# 411618_029_3_7.net
KiCad netlist of a schematic drawn in Altium Designer
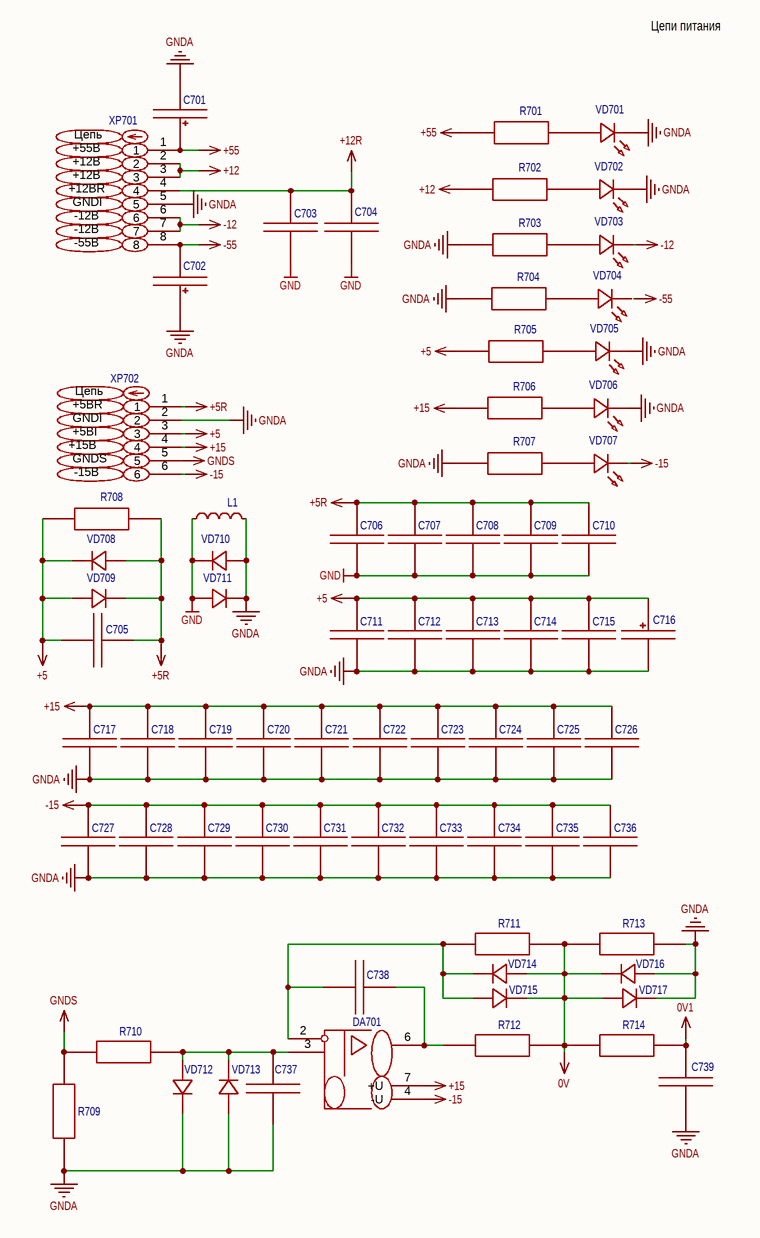
[diagram p0: УШЯИ.411618.029Э Э3 Лист 7.schdoc]

(export (version "E")
  (design (tool "Eeschema 10.0.6"))
  (components
    (comp (ref "C701")
      (value "ECAP (К50-35), 4.7мкФ, 100В, 105°C, 5x11, p:2мм")
      (footprint "CAP-TH_BD5.0-P2.00-D0.8-FD")
      (fields (field (name "MANUFACTURER") "Chengx") (field (name "CONTRIBUTOR") "jordanjin"))
      (libsource (lib "altium-import") (part "root_2_ECAP (К50-35), 4.7мкФ, 100В, 105°C, 5x11, p{colon}2мм_"))
    )
    (comp (ref "C702")
      (value "ECAP (К50-35), 4.7мкФ, 100В, 105°C, 5x11, p:2мм")
      (footprint "CAP-TH_BD5.0-P2.00-D0.8-FD")
      (fields (field (name "MANUFACTURER") "Chengx") (field (name "CONTRIBUTOR") "jordanjin"))
      (libsource (lib "altium-import") (part "root_2_ECAP (К50-35), 4.7мкФ, 100В, 105°C, 5x11, p{colon}2мм_"))
    )
    (comp (ref "C703")
      (value "Конденсатор SMD 1мкФ 100В X7R 10% [0805]")
      (footprint "C0805")
      (fields (field (name "MANUFACTURER PART") "C0805") (field (name "CONTRIBUTOR") "jordanjin"))
      (libsource (lib "altium-import") (part "root_1_Конденсатор SMD 1мкФ 100В X7R 10% [0805]_"))
    )
    (comp (ref "C704")
      (value "Конденсатор SMD 1мкФ 100В X7R 10% [0805]")
      (footprint "C0805")
      (fields (field (name "MANUFACTURER PART") "C0805") (field (name "CONTRIBUTOR") "jordanjin"))
      (libsource (lib "altium-import") (part "root_1_Конденсатор SMD 1мкФ 100В X7R 10% [0805]_"))
    )
    (comp (ref "C705")
      (value "Конденсатор SMD 3300пФ 100В X7R 10% [0805]")
      (footprint "C0805")
      (fields (field (name "MANUFACTURER PART") "C0805") (field (name "CONTRIBUTOR") "jordanjin"))
      (libsource (lib "altium-import") (part "root_2_Конденсатор SMD 3300пФ 100В X7R 10% [0805]_"))
    )
    (comp (ref "C706")
      (value "Конденсатор SMD 0,33мкФ 100В X7R 10% [0805]")
      (footprint "C0805")
      (fields (field (name "MANUFACTURER PART") "C0805") (field (name "CONTRIBUTOR") "jordanjin"))
      (libsource (lib "altium-import") (part "root_1_Конденсатор SMD 0,33мкФ 100В X7R 10% [0805]_"))
    )
    (comp (ref "C707")
      (value "Конденсатор SMD 0,33мкФ 100В X7R 10% [0805]")
      (footprint "C0805")
      (fields (field (name "MANUFACTURER PART") "C0805") (field (name "CONTRIBUTOR") "jordanjin"))
      (libsource (lib "altium-import") (part "root_1_Конденсатор SMD 0,33мкФ 100В X7R 10% [0805]_"))
    )
    (comp (ref "C708")
      (value "Конденсатор SMD 0,33мкФ 100В X7R 10% [0805]")
      (footprint "C0805")
      (fields (field (name "MANUFACTURER PART") "C0805") (field (name "CONTRIBUTOR") "jordanjin"))
      (libsource (lib "altium-import") (part "root_1_Конденсатор SMD 0,33мкФ 100В X7R 10% [0805]_"))
    )
    (comp (ref "C709")
      (value "Конденсатор SMD 0,33мкФ 100В X7R 10% [0805]")
      (footprint "C0805")
      (fields (field (name "MANUFACTURER PART") "C0805") (field (name "CONTRIBUTOR") "jordanjin"))
      (libsource (lib "altium-import") (part "root_1_Конденсатор SMD 0,33мкФ 100В X7R 10% [0805]_"))
    )
    (comp (ref "C710")
      (value "Конденсатор SMD 0,33мкФ 100В X7R 10% [0805]")
      (footprint "C0805")
      (fields (field (name "MANUFACTURER PART") "C0805") (field (name "CONTRIBUTOR") "jordanjin"))
      (libsource (lib "altium-import") (part "root_1_Конденсатор SMD 0,33мкФ 100В X7R 10% [0805]_"))
    )
    (comp (ref "C711")
      (value "Конденсатор SMD 0,33мкФ 100В X7R 10% [0805]")
      (footprint "C0805")
      (fields (field (name "MANUFACTURER PART") "C0805") (field (name "CONTRIBUTOR") "jordanjin"))
      (libsource (lib "altium-import") (part "root_1_Конденсатор SMD 0,33мкФ 100В X7R 10% [0805]_"))
    )
    (comp (ref "C712")
      (value "Конденсатор SMD 0,33мкФ 100В X7R 10% [0805]")
      (footprint "C0805")
      (fields (field (name "MANUFACTURER PART") "C0805") (field (name "CONTRIBUTOR") "jordanjin"))
      (libsource (lib "altium-import") (part "root_1_Конденсатор SMD 0,33мкФ 100В X7R 10% [0805]_"))
    )
    (comp (ref "C713")
      (value "Конденсатор SMD 0,33мкФ 100В X7R 10% [0805]")
      (footprint "C0805")
      (fields (field (name "MANUFACTURER PART") "C0805") (field (name "CONTRIBUTOR") "jordanjin"))
      (libsource (lib "altium-import") (part "root_1_Конденсатор SMD 0,33мкФ 100В X7R 10% [0805]_"))
    )
    (comp (ref "C714")
      (value "Конденсатор SMD 0,33мкФ 100В X7R 10% [0805]")
      (footprint "C0805")
      (fields (field (name "MANUFACTURER PART") "C0805") (field (name "CONTRIBUTOR") "jordanjin"))
      (libsource (lib "altium-import") (part "root_1_Конденсатор SMD 0,33мкФ 100В X7R 10% [0805]_"))
    )
    (comp (ref "C715")
      (value "Конденсатор SMD 0,33мкФ 100В X7R 10% [0805]")
      (footprint "C0805")
      (fields (field (name "MANUFACTURER PART") "C0805") (field (name "CONTRIBUTOR") "jordanjin"))
      (libsource (lib "altium-import") (part "root_1_Конденсатор SMD 0,33мкФ 100В X7R 10% [0805]_"))
    )
    (comp (ref "C716")
      (value "ECAP (К50-35), 4.7мкФ, 100В, 105°C, 5x11, p:2мм")
      (footprint "CAP-TH_BD5.0-P2.00-D0.8-FD")
      (fields (field (name "MANUFACTURER") "Chengx") (field (name "CONTRIBUTOR") "jordanjin"))
      (libsource (lib "altium-import") (part "root_0_ECAP (К50-35), 4.7мкФ, 100В, 105°C, 5x11, p{colon}2мм_"))
    )
    (comp (ref "C717")
      (value "Конденсатор SMD 0,33мкФ 100В X7R 10% [0805]")
      (footprint "C0805")
      (fields (field (name "MANUFACTURER PART") "C0805") (field (name "CONTRIBUTOR") "jordanjin"))
      (libsource (lib "altium-import") (part "root_1_Конденсатор SMD 0,33мкФ 100В X7R 10% [0805]_"))
    )
    (comp (ref "C718")
      (value "Конденсатор SMD 0,33мкФ 100В X7R 10% [0805]")
      (footprint "C0805")
      (fields (field (name "MANUFACTURER PART") "C0805") (field (name "CONTRIBUTOR") "jordanjin"))
      (libsource (lib "altium-import") (part "root_1_Конденсатор SMD 0,33мкФ 100В X7R 10% [0805]_"))
    )
    (comp (ref "C719")
      (value "Конденсатор SMD 0,33мкФ 100В X7R 10% [0805]")
      (footprint "C0805")
      (fields (field (name "MANUFACTURER PART") "C0805") (field (name "CONTRIBUTOR") "jordanjin"))
      (libsource (lib "altium-import") (part "root_1_Конденсатор SMD 0,33мкФ 100В X7R 10% [0805]_"))
    )
    (comp (ref "C720")
      (value "Конденсатор SMD 0,33мкФ 100В X7R 10% [0805]")
      (footprint "C0805")
      (fields (field (name "MANUFACTURER PART") "C0805") (field (name "CONTRIBUTOR") "jordanjin"))
      (libsource (lib "altium-import") (part "root_1_Конденсатор SMD 0,33мкФ 100В X7R 10% [0805]_"))
    )
    (comp (ref "C721")
      (value "Конденсатор SMD 0,33мкФ 100В X7R 10% [0805]")
      (footprint "C0805")
      (fields (field (name "MANUFACTURER PART") "C0805") (field (name "CONTRIBUTOR") "jordanjin"))
      (libsource (lib "altium-import") (part "root_1_Конденсатор SMD 0,33мкФ 100В X7R 10% [0805]_"))
    )
    (comp (ref "C722")
      (value "Конденсатор SMD 0,33мкФ 100В X7R 10% [0805]")
      (footprint "C0805")
      (fields (field (name "MANUFACTURER PART") "C0805") (field (name "CONTRIBUTOR") "jordanjin"))
      (libsource (lib "altium-import") (part "root_1_Конденсатор SMD 0,33мкФ 100В X7R 10% [0805]_"))
    )
    (comp (ref "C723")
      (value "Конденсатор SMD 0,33мкФ 100В X7R 10% [0805]")
      (footprint "C0805")
      (fields (field (name "MANUFACTURER PART") "C0805") (field (name "CONTRIBUTOR") "jordanjin"))
      (libsource (lib "altium-import") (part "root_1_Конденсатор SMD 0,33мкФ 100В X7R 10% [0805]_"))
    )
    (comp (ref "C724")
      (value "Конденсатор SMD 0,33мкФ 100В X7R 10% [0805]")
      (footprint "C0805")
      (fields (field (name "MANUFACTURER PART") "C0805") (field (name "CONTRIBUTOR") "jordanjin"))
      (libsource (lib "altium-import") (part "root_1_Конденсатор SMD 0,33мкФ 100В X7R 10% [0805]_"))
    )
    (comp (ref "C725")
      (value "Конденсатор SMD 0,33мкФ 100В X7R 10% [0805]")
      (footprint "C0805")
      (fields (field (name "MANUFACTURER PART") "C0805") (field (name "CONTRIBUTOR") "jordanjin"))
      (libsource (lib "altium-import") (part "root_1_Конденсатор SMD 0,33мкФ 100В X7R 10% [0805]_"))
    )
    (comp (ref "C726")
      (value "Конденсатор SMD 0,33мкФ 100В X7R 10% [0805]")
      (footprint "C0805")
      (fields (field (name "MANUFACTURER PART") "C0805") (field (name "CONTRIBUTOR") "jordanjin"))
      (libsource (lib "altium-import") (part "root_1_Конденсатор SMD 0,33мкФ 100В X7R 10% [0805]_"))
    )
    (comp (ref "C727")
      (value "Конденсатор SMD 0,33мкФ 100В X7R 10% [0805]")
      (footprint "C0805")
      (fields (field (name "MANUFACTURER PART") "C0805") (field (name "CONTRIBUTOR") "jordanjin"))
      (libsource (lib "altium-import") (part "root_1_Конденсатор SMD 0,33мкФ 100В X7R 10% [0805]_"))
    )
    (comp (ref "C728")
      (value "Конденсатор SMD 0,33мкФ 100В X7R 10% [0805]")
      (footprint "C0805")
      (fields (field (name "MANUFACTURER PART") "C0805") (field (name "CONTRIBUTOR") "jordanjin"))
      (libsource (lib "altium-import") (part "root_1_Конденсатор SMD 0,33мкФ 100В X7R 10% [0805]_"))
    )
    (comp (ref "C729")
      (value "Конденсатор SMD 0,33мкФ 100В X7R 10% [0805]")
      (footprint "C0805")
      (fields (field (name "MANUFACTURER PART") "C0805") (field (name "CONTRIBUTOR") "jordanjin"))
      (libsource (lib "altium-import") (part "root_1_Конденсатор SMD 0,33мкФ 100В X7R 10% [0805]_"))
    )
    (comp (ref "C730")
      (value "Конденсатор SMD 0,33мкФ 100В X7R 10% [0805]")
      (footprint "C0805")
      (fields (field (name "MANUFACTURER PART") "C0805") (field (name "CONTRIBUTOR") "jordanjin"))
      (libsource (lib "altium-import") (part "root_1_Конденсатор SMD 0,33мкФ 100В X7R 10% [0805]_"))
    )
    (comp (ref "C731")
      (value "Конденсатор SMD 0,33мкФ 100В X7R 10% [0805]")
      (footprint "C0805")
      (fields (field (name "MANUFACTURER PART") "C0805") (field (name "CONTRIBUTOR") "jordanjin"))
      (libsource (lib "altium-import") (part "root_1_Конденсатор SMD 0,33мкФ 100В X7R 10% [0805]_"))
    )
    (comp (ref "C732")
      (value "Конденсатор SMD 0,33мкФ 100В X7R 10% [0805]")
      (footprint "C0805")
      (fields (field (name "MANUFACTURER PART") "C0805") (field (name "CONTRIBUTOR") "jordanjin"))
      (libsource (lib "altium-import") (part "root_1_Конденсатор SMD 0,33мкФ 100В X7R 10% [0805]_"))
    )
    (comp (ref "C733")
      (value "Конденсатор SMD 0,33мкФ 100В X7R 10% [0805]")
      (footprint "C0805")
      (fields (field (name "MANUFACTURER PART") "C0805") (field (name "CONTRIBUTOR") "jordanjin"))
      (libsource (lib "altium-import") (part "root_1_Конденсатор SMD 0,33мкФ 100В X7R 10% [0805]_"))
    )
    (comp (ref "C734")
      (value "Конденсатор SMD 0,33мкФ 100В X7R 10% [0805]")
      (footprint "C0805")
      (fields (field (name "MANUFACTURER PART") "C0805") (field (name "CONTRIBUTOR") "jordanjin"))
      (libsource (lib "altium-import") (part "root_1_Конденсатор SMD 0,33мкФ 100В X7R 10% [0805]_"))
    )
    (comp (ref "C735")
      (value "Конденсатор SMD 0,33мкФ 100В X7R 10% [0805]")
      (footprint "C0805")
      (fields (field (name "MANUFACTURER PART") "C0805") (field (name "CONTRIBUTOR") "jordanjin"))
      (libsource (lib "altium-import") (part "root_1_Конденсатор SMD 0,33мкФ 100В X7R 10% [0805]_"))
    )
    (comp (ref "C736")
      (value "Конденсатор SMD 0,33мкФ 100В X7R 10% [0805]")
      (footprint "C0805")
      (fields (field (name "MANUFACTURER PART") "C0805") (field (name "CONTRIBUTOR") "jordanjin"))
      (libsource (lib "altium-import") (part "root_1_Конденсатор SMD 0,33мкФ 100В X7R 10% [0805]_"))
    )
    (comp (ref "C737")
      (value "Конденсатор SMD 2,2мкФ 100В X7R 10% [0805]")
      (footprint "C0805")
      (fields (field (name "MANUFACTURER PART") "C0805") (field (name "CONTRIBUTOR") "jordanjin"))
      (libsource (lib "altium-import") (part "root_3_Конденсатор SMD 2,2мкФ 100В X7R 10% [0805]_"))
    )
    (comp (ref "C738")
      (value "Конденсатор SMD 240пФ 100В X7R 10% [0805]")
      (footprint "C0805")
      (fields (field (name "MANUFACTURER PART") "C0805") (field (name "CONTRIBUTOR") "jordanjin"))
      (libsource (lib "altium-import") (part "root_0_Конденсатор SMD 240пФ 100В X7R 10% [0805]_"))
    )
    (comp (ref "C739")
      (value "Конденсатор SMD 680пФ 100В X7R 10% [0805]")
      (footprint "C0805")
      (fields (field (name "MANUFACTURER PART") "C0805") (field (name "CONTRIBUTOR") "jordanjin"))
      (libsource (lib "altium-import") (part "root_1_Конденсатор SMD 680пФ 100В X7R 10% [0805]_"))
    )
    (comp (ref "DA701")
      (value "Операционный усилитель AD8671ARZ [SOIC-8]")
      (footprint "SOIC-8_L4.9-W3.9-P1.27-LS6.0-BL")
      (fields
        (field (name "MANUFACTURER") "Analog Devices")
        (field (name "MANUFACTURER PART") "AD8671ARZ-REEL7")
        (field (name "CONTRIBUTOR") "jordanjin")
      )
      (libsource (lib "altium-import") (part "root_0_Операционный усилитель AD8671ARZ [SOIC-8]_"))
    )
    (comp (ref "L1")
      (value "Дроссель LQH55DN101M01 [2220]")
      (footprint "L2220")
      (fields (field (name "MANUFACTURER") "muRata(村田)") (field (name "MANUFACTURER PART") "LQH55DN101M01"))
      (libsource (lib "altium-import") (part "root_0_Дроссель LQH55DN101M01 [2220]_"))
    )
    (comp (ref "R701")
      (value "Резистор 3кОм 0,125Вт 1% [0805]")
      (footprint "R0805")
      (fields (field (name "MANUFACTURER PART") "R0805") (field (name "CONTRIBUTOR") "jordanjin"))
      (libsource (lib "altium-import") (part "root_0_Резистор 3кОм 0,125Вт 1% [0805]_"))
    )
    (comp (ref "R702")
      (value "Резистор 510Ом 0,125Вт 1% [0805]")
      (footprint "R0805")
      (fields (field (name "MANUFACTURER PART") "R0805") (field (name "CONTRIBUTOR") "jordanjin"))
      (libsource (lib "altium-import") (part "root_0_Резистор 510Ом 0,125Вт 1% [0805]_"))
    )
    (comp (ref "R703")
      (value "Резистор 510Ом 0,125Вт 1% [0805]")
      (footprint "R0805")
      (fields (field (name "MANUFACTURER PART") "R0805") (field (name "CONTRIBUTOR") "jordanjin"))
      (libsource (lib "altium-import") (part "root_0_Резистор 510Ом 0,125Вт 1% [0805]_"))
    )
    (comp (ref "R704")
      (value "Резистор 3кОм 0,125Вт 1% [0805]")
      (footprint "R0805")
      (fields (field (name "MANUFACTURER PART") "R0805") (field (name "CONTRIBUTOR") "jordanjin"))
      (libsource (lib "altium-import") (part "root_0_Резистор 3кОм 0,125Вт 1% [0805]_"))
    )
    (comp (ref "R705")
      (value "Резистор 150Ом 0,125Вт 1% [0805]")
      (footprint "R0805")
      (fields (field (name "MANUFACTURER PART") "R0805") (field (name "CONTRIBUTOR") "jordanjin"))
      (libsource (lib "altium-import") (part "root_0_Резистор 150Ом 0,125Вт 1% [0805]_"))
    )
    (comp (ref "R706")
      (value "Резистор 1кОм 0,125Вт 1% [0805]")
      (footprint "R0805")
      (fields (field (name "MANUFACTURER PART") "R0805") (field (name "CONTRIBUTOR") "jordanjin"))
      (libsource (lib "altium-import") (part "root_0_Резистор 1кОм 0,125Вт 1% [0805]_"))
    )
    (comp (ref "R707")
      (value "Резистор 1кОм 0,125Вт 1% [0805]")
      (footprint "R0805")
      (fields (field (name "MANUFACTURER PART") "R0805") (field (name "CONTRIBUTOR") "jordanjin"))
      (libsource (lib "altium-import") (part "root_0_Резистор 1кОм 0,125Вт 1% [0805]_"))
    )
    (comp (ref "R708")
      (value "Резистор 240Ом 0,125Вт 1% [0805]")
      (footprint "R0805")
      (fields (field (name "MANUFACTURER PART") "R0805") (field (name "CONTRIBUTOR") "jordanjin"))
      (libsource (lib "altium-import") (part "root_0_Резистор 240Ом 0,125Вт 1% [0805]_"))
    )
    (comp (ref "R709")
      (value "Резистор 1,1кОм 0,125Вт 1% [0805]")
      (footprint "R0805")
      (fields (field (name "MANUFACTURER PART") "R0805") (field (name "CONTRIBUTOR") "jordanjin"))
      (libsource (lib "altium-import") (part "root_3_Резистор 1,1кОм 0,125Вт 1% [0805]_"))
    )
    (comp (ref "R710")
      (value "Резистор 1,1кОм 0,125Вт 1% [0805]")
      (footprint "R0805")
      (fields (field (name "MANUFACTURER PART") "R0805") (field (name "CONTRIBUTOR") "jordanjin"))
      (libsource (lib "altium-import") (part "root_2_Резистор 1,1кОм 0,125Вт 1% [0805]_"))
    )
    (comp (ref "R711")
      (value "Резистор 1,1кОм 0,125Вт 1% [0805]")
      (footprint "R0805")
      (fields (field (name "MANUFACTURER PART") "R0805") (field (name "CONTRIBUTOR") "jordanjin"))
      (libsource (lib "altium-import") (part "root_2_Резистор 1,1кОм 0,125Вт 1% [0805]_"))
    )
    (comp (ref "R712")
      (value "Резистор 22 кОм 0,125Вт 1% [0805]")
      (footprint "R0805")
      (fields (field (name "MANUFACTURER PART") "R0805") (field (name "CONTRIBUTOR") "jordanjin"))
      (libsource (lib "altium-import") (part "root_2_Резистор 22 кОм 0,125Вт 1% [0805]_"))
    )
    (comp (ref "R713")
      (value "Резистор 330Ом 0,125Вт 1% [0805]")
      (footprint "R0805")
      (fields (field (name "MANUFACTURER PART") "R0805") (field (name "CONTRIBUTOR") "jordanjin"))
      (libsource (lib "altium-import") (part "root_2_Резистор 330Ом 0,125Вт 1% [0805]_"))
    )
    (comp (ref "R714")
      (value "Резистор 22 кОм 0,125Вт 1% [0805]")
      (footprint "R0805")
      (fields (field (name "MANUFACTURER PART") "R0805") (field (name "CONTRIBUTOR") "jordanjin"))
      (libsource (lib "altium-import") (part "root_2_Резистор 22 кОм 0,125Вт 1% [0805]_"))
    )
    (comp (ref "VD701")
      (value "Светодиод YLED0805YG [0805]")
      (footprint "LED0805-R-RD")
      (fields
        (field (name "MANUFACTURER") "YONGYUTAI(永裕泰)")
        (field (name "MANUFACTURER PART") "YLED0805YG")
        (field (name "CONTRIBUTOR") "lcsc")
      )
      (libsource (lib "altium-import") (part "root_2_Светодиод YLED0805YG [0805]_"))
    )
    (comp (ref "VD702")
      (value "Светодиод YLED0805YG [0805]")
      (footprint "LED0805-R-RD")
      (fields
        (field (name "MANUFACTURER") "YONGYUTAI(永裕泰)")
        (field (name "MANUFACTURER PART") "YLED0805YG")
        (field (name "CONTRIBUTOR") "lcsc")
      )
      (libsource (lib "altium-import") (part "root_2_Светодиод YLED0805YG [0805]_"))
    )
    (comp (ref "VD703")
      (value "Светодиод YLED0805YG [0805]")
      (footprint "LED0805-R-RD")
      (fields
        (field (name "MANUFACTURER") "YONGYUTAI(永裕泰)")
        (field (name "MANUFACTURER PART") "YLED0805YG")
        (field (name "CONTRIBUTOR") "lcsc")
      )
      (libsource (lib "altium-import") (part "root_2_Светодиод YLED0805YG [0805]_"))
    )
    (comp (ref "VD704")
      (value "Светодиод YLED0805YG [0805]")
      (footprint "LED0805-R-RD")
      (fields
        (field (name "MANUFACTURER") "YONGYUTAI(永裕泰)")
        (field (name "MANUFACTURER PART") "YLED0805YG")
        (field (name "CONTRIBUTOR") "lcsc")
      )
      (libsource (lib "altium-import") (part "root_2_Светодиод YLED0805YG [0805]_"))
    )
    (comp (ref "VD705")
      (value "Светодиод YLED0805YG [0805]")
      (footprint "LED0805-R-RD")
      (fields
        (field (name "MANUFACTURER") "YONGYUTAI(永裕泰)")
        (field (name "MANUFACTURER PART") "YLED0805YG")
        (field (name "CONTRIBUTOR") "lcsc")
      )
      (libsource (lib "altium-import") (part "root_2_Светодиод YLED0805YG [0805]_"))
    )
    (comp (ref "VD706")
      (value "Светодиод YLED0805YG [0805]")
      (footprint "LED0805-R-RD")
      (fields
        (field (name "MANUFACTURER") "YONGYUTAI(永裕泰)")
        (field (name "MANUFACTURER PART") "YLED0805YG")
        (field (name "CONTRIBUTOR") "lcsc")
      )
      (libsource (lib "altium-import") (part "root_2_Светодиод YLED0805YG [0805]_"))
    )
    (comp (ref "VD707")
      (value "Светодиод YLED0805YG [0805]")
      (footprint "LED0805-R-RD")
      (fields
        (field (name "MANUFACTURER") "YONGYUTAI(永裕泰)")
        (field (name "MANUFACTURER PART") "YLED0805YG")
        (field (name "CONTRIBUTOR") "lcsc")
      )
      (libsource (lib "altium-import") (part "root_2_Светодиод YLED0805YG [0805]_"))
    )
    (comp (ref "VD708")
      (value "Диод импульсный 1N4448 [SOD-123]")
      (footprint "SOD-123_L2.7-W1.6-LS3.7-RD-1")
      (fields
        (field (name "MANUFACTURER") "YANGJIE")
        (field (name "MANUFACTURER PART") "1N4448WQ")
        (field (name "CONTRIBUTOR") "jordanjin")
      )
      (libsource (lib "altium-import") (part "root_0_Диод импульсный 1N4448 [SOD-123]_"))
    )
    (comp (ref "VD709")
      (value "Диод импульсный 1N4448 [SOD-123]")
      (footprint "SOD-123_L2.7-W1.6-LS3.7-RD-1")
      (fields
        (field (name "MANUFACTURER") "YANGJIE")
        (field (name "MANUFACTURER PART") "1N4448WQ")
        (field (name "CONTRIBUTOR") "jordanjin")
      )
      (libsource (lib "altium-import") (part "root_2_Диод импульсный 1N4448 [SOD-123]_"))
    )
    (comp (ref "VD710")
      (value "Диод импульсный 1N4448 [SOD-123]")
      (footprint "SOD-123_L2.7-W1.6-LS3.7-RD-1")
      (fields
        (field (name "MANUFACTURER") "YANGJIE")
        (field (name "MANUFACTURER PART") "1N4448WQ")
        (field (name "CONTRIBUTOR") "jordanjin")
      )
      (libsource (lib "altium-import") (part "root_0_Диод импульсный 1N4448 [SOD-123]_"))
    )
    (comp (ref "VD711")
      (value "Диод импульсный 1N4448 [SOD-123]")
      (footprint "SOD-123_L2.7-W1.6-LS3.7-RD-1")
      (fields
        (field (name "MANUFACTURER") "YANGJIE")
        (field (name "MANUFACTURER PART") "1N4448WQ")
        (field (name "CONTRIBUTOR") "jordanjin")
      )
      (libsource (lib "altium-import") (part "root_2_Диод импульсный 1N4448 [SOD-123]_"))
    )
    (comp (ref "VD712")
      (value "Диод импульсный 1N4448 [SOD-123]")
      (footprint "SOD-123_L2.7-W1.6-LS3.7-RD-1")
      (fields
        (field (name "MANUFACTURER") "YANGJIE")
        (field (name "MANUFACTURER PART") "1N4448WQ")
        (field (name "CONTRIBUTOR") "jordanjin")
      )
      (libsource (lib "altium-import") (part "root_1_Диод импульсный 1N4448 [SOD-123]_"))
    )
    (comp (ref "VD713")
      (value "Диод импульсный 1N4448 [SOD-123]")
      (footprint "SOD-123_L2.7-W1.6-LS3.7-RD-1")
      (fields
        (field (name "MANUFACTURER") "YANGJIE")
        (field (name "MANUFACTURER PART") "1N4448WQ")
        (field (name "CONTRIBUTOR") "jordanjin")
      )
      (libsource (lib "altium-import") (part "root_3_Диод импульсный 1N4448 [SOD-123]_"))
    )
    (comp (ref "VD714")
      (value "Диод импульсный 1N4448 [SOD-123]")
      (footprint "SOD-123_L2.7-W1.6-LS3.7-RD-1")
      (fields
        (field (name "MANUFACTURER") "YANGJIE")
        (field (name "MANUFACTURER PART") "1N4448WQ")
        (field (name "CONTRIBUTOR") "jordanjin")
      )
      (libsource (lib "altium-import") (part "root_0_Диод импульсный 1N4448 [SOD-123]_"))
    )
    (comp (ref "VD715")
      (value "Диод импульсный 1N4448 [SOD-123]")
      (footprint "SOD-123_L2.7-W1.6-LS3.7-RD-1")
      (fields
        (field (name "MANUFACTURER") "YANGJIE")
        (field (name "MANUFACTURER PART") "1N4448WQ")
        (field (name "CONTRIBUTOR") "jordanjin")
      )
      (libsource (lib "altium-import") (part "root_2_Диод импульсный 1N4448 [SOD-123]_"))
    )
    (comp (ref "VD716")
      (value "Диод импульсный 1N4448 [SOD-123]")
      (footprint "SOD-123_L2.7-W1.6-LS3.7-RD-1")
      (fields
        (field (name "MANUFACTURER") "YANGJIE")
        (field (name "MANUFACTURER PART") "1N4448WQ")
        (field (name "CONTRIBUTOR") "jordanjin")
      )
      (libsource (lib "altium-import") (part "root_0_Диод импульсный 1N4448 [SOD-123]_"))
    )
    (comp (ref "VD717")
      (value "Диод импульсный 1N4448 [SOD-123]")
      (footprint "SOD-123_L2.7-W1.6-LS3.7-RD-1")
      (fields
        (field (name "MANUFACTURER") "YANGJIE")
        (field (name "MANUFACTURER PART") "1N4448WQ")
        (field (name "CONTRIBUTOR") "jordanjin")
      )
      (libsource (lib "altium-import") (part "root_2_Диод импульсный 1N4448 [SOD-123]_"))
    )
    (comp (ref "XP701")
      (value "Вилка на плату 280373-2 шаг 2.54мм")
      (footprint "CONN-TH_8P-P2.54_280373-1")
      (fields
        (field (name "MANUFACTURER") "TE Connectivity")
        (field (name "MANUFACTURER PART") "280373-2")
        (field (name "CONTRIBUTOR") "jordanjin")
      )
      (libsource (lib "altium-import") (part "root_0_Вилка на плату 280373-2 шаг 2.54мм_"))
    )
    (comp (ref "XP702")
      (value "Вилка на плату 280372-2 шаг 2.54мм")
      (footprint "CONN-TH_DIP-6-2.54")
      (fields
        (field (name "MANUFACTURER") "TE Connectivity")
        (field (name "MANUFACTURER PART") "280372-2")
        (field (name "CONTRIBUTOR") "jordanjin")
      )
      (libsource (lib "altium-import") (part "root_0_Вилка на плату 280372-2 шаг 2.54мм_"))
    )
  )
  (nets
    (net (code "1") (name "+5") (class "Default")
      (node (ref "C705") (pin "2") (pinfunction "2_2") (pintype "passive"))
      (node (ref "C711") (pin "2") (pinfunction "2_2") (pintype "passive"))
      (node (ref "C712") (pin "2") (pinfunction "2_2") (pintype "passive"))
      (node (ref "C713") (pin "2") (pinfunction "2_2") (pintype "passive"))
      (node (ref "C714") (pin "2") (pinfunction "2_2") (pintype "passive"))
      (node (ref "C715") (pin "2") (pinfunction "2_2") (pintype "passive"))
      (node (ref "C716") (pin "1") (pinfunction "1_1") (pintype "passive"))
      (node (ref "R705") (pin "1") (pinfunction "1_1") (pintype "passive"))
      (node (ref "R708") (pin "1") (pinfunction "1_1") (pintype "passive"))
      (node (ref "VD708") (pin "1") (pinfunction "C_1") (pintype "passive"))
      (node (ref "VD709") (pin "2") (pinfunction "A_2") (pintype "passive"))
      (node (ref "XP702") (pin "3") (pinfunction "3_3") (pintype "passive"))
    )
    (net (code "2") (name "+5R") (class "Default")
      (node (ref "C705") (pin "1") (pinfunction "1_1") (pintype "passive"))
      (node (ref "C706") (pin "2") (pinfunction "2_2") (pintype "passive"))
      (node (ref "C707") (pin "2") (pinfunction "2_2") (pintype "passive"))
      (node (ref "C708") (pin "2") (pinfunction "2_2") (pintype "passive"))
      (node (ref "C709") (pin "2") (pinfunction "2_2") (pintype "passive"))
      (node (ref "C710") (pin "2") (pinfunction "2_2") (pintype "passive"))
      (node (ref "R708") (pin "2") (pinfunction "2_2") (pintype "passive"))
      (node (ref "VD708") (pin "2") (pinfunction "A_2") (pintype "passive"))
      (node (ref "VD709") (pin "1") (pinfunction "C_1") (pintype "passive"))
      (node (ref "XP702") (pin "1") (pinfunction "1_1") (pintype "passive"))
    )
    (net (code "3") (name "+12") (class "Default")
      (node (ref "R702") (pin "1") (pinfunction "1_1") (pintype "passive"))
      (node (ref "XP701") (pin "2") (pinfunction "2_2") (pintype "passive"))
      (node (ref "XP701") (pin "3") (pinfunction "3_3") (pintype "passive"))
    )
    (net (code "4") (name "+12R") (class "Default")
      (node (ref "C703") (pin "2") (pinfunction "2_2") (pintype "passive"))
      (node (ref "C704") (pin "2") (pinfunction "2_2") (pintype "passive"))
      (node (ref "XP701") (pin "4") (pinfunction "4_4") (pintype "passive"))
    )
    (net (code "5") (name "+15") (class "Default")
      (node (ref "C717") (pin "2") (pinfunction "2_2") (pintype "passive"))
      (node (ref "C718") (pin "2") (pinfunction "2_2") (pintype "passive"))
      (node (ref "C719") (pin "2") (pinfunction "2_2") (pintype "passive"))
      (node (ref "C720") (pin "2") (pinfunction "2_2") (pintype "passive"))
      (node (ref "C721") (pin "2") (pinfunction "2_2") (pintype "passive"))
      (node (ref "C722") (pin "2") (pinfunction "2_2") (pintype "passive"))
      (node (ref "C723") (pin "2") (pinfunction "2_2") (pintype "passive"))
      (node (ref "C724") (pin "2") (pinfunction "2_2") (pintype "passive"))
      (node (ref "C725") (pin "2") (pinfunction "2_2") (pintype "passive"))
      (node (ref "C726") (pin "2") (pinfunction "2_2") (pintype "passive"))
      (node (ref "DA701") (pin "7") (pinfunction "+U_7") (pintype "passive"))
      (node (ref "R706") (pin "1") (pinfunction "1_1") (pintype "passive"))
      (node (ref "XP702") (pin "4") (pinfunction "4_4") (pintype "passive"))
    )
    (net (code "6") (name "+55") (class "Default")
      (node (ref "C701") (pin "1") (pinfunction "1_1") (pintype "passive"))
      (node (ref "R701") (pin "1") (pinfunction "1_1") (pintype "passive"))
      (node (ref "XP701") (pin "1") (pinfunction "1_1") (pintype "passive"))
    )
    (net (code "7") (name "-12") (class "Default")
      (node (ref "VD703") (pin "2") (pinfunction "2_2") (pintype "passive"))
      (node (ref "XP701") (pin "6") (pinfunction "6_6") (pintype "passive"))
      (node (ref "XP701") (pin "7") (pinfunction "7_7") (pintype "passive"))
    )
    (net (code "8") (name "-15") (class "Default")
      (node (ref "C727") (pin "2") (pinfunction "2_2") (pintype "passive"))
      (node (ref "C728") (pin "2") (pinfunction "2_2") (pintype "passive"))
      (node (ref "C729") (pin "2") (pinfunction "2_2") (pintype "passive"))
      (node (ref "C730") (pin "2") (pinfunction "2_2") (pintype "passive"))
      (node (ref "C731") (pin "2") (pinfunction "2_2") (pintype "passive"))
      (node (ref "C732") (pin "2") (pinfunction "2_2") (pintype "passive"))
      (node (ref "C733") (pin "2") (pinfunction "2_2") (pintype "passive"))
      (node (ref "C734") (pin "2") (pinfunction "2_2") (pintype "passive"))
      (node (ref "C735") (pin "2") (pinfunction "2_2") (pintype "passive"))
      (node (ref "C736") (pin "2") (pinfunction "2_2") (pintype "passive"))
      (node (ref "DA701") (pin "4") (pinfunction "-U_4") (pintype "passive"))
      (node (ref "VD707") (pin "2") (pinfunction "2_2") (pintype "passive"))
      (node (ref "XP702") (pin "6") (pinfunction "6_6") (pintype "passive"))
    )
    (net (code "9") (name "-55") (class "Default")
      (node (ref "C702") (pin "2") (pinfunction "2_2") (pintype "passive"))
      (node (ref "XP701") (pin "8") (pinfunction "8_8") (pintype "passive"))
    )
    (net (code "10") (name "0V") (class "Default")
      (node (ref "R711") (pin "1") (pinfunction "1_1") (pintype "passive"))
      (node (ref "R712") (pin "1") (pinfunction "1_1") (pintype "passive"))
      (node (ref "R713") (pin "2") (pinfunction "2_2") (pintype "passive"))
      (node (ref "R714") (pin "2") (pinfunction "2_2") (pintype "passive"))
      (node (ref "VD714") (pin "2") (pinfunction "A_2") (pintype "passive"))
      (node (ref "VD715") (pin "1") (pinfunction "C_1") (pintype "passive"))
      (node (ref "VD716") (pin "1") (pinfunction "C_1") (pintype "passive"))
      (node (ref "VD717") (pin "2") (pinfunction "A_2") (pintype "passive"))
    )
    (net (code "11") (name "0V1") (class "Default")
      (node (ref "C739") (pin "2") (pinfunction "2_2") (pintype "passive"))
      (node (ref "R714") (pin "1") (pinfunction "1_1") (pintype "passive"))
    )
    (net (code "12") (name "GND") (class "Default")
      (node (ref "C703") (pin "1") (pinfunction "1_1") (pintype "passive"))
      (node (ref "C704") (pin "1") (pinfunction "1_1") (pintype "passive"))
      (node (ref "C706") (pin "1") (pinfunction "1_1") (pintype "passive"))
      (node (ref "C707") (pin "1") (pinfunction "1_1") (pintype "passive"))
      (node (ref "C708") (pin "1") (pinfunction "1_1") (pintype "passive"))
      (node (ref "C709") (pin "1") (pinfunction "1_1") (pintype "passive"))
      (node (ref "C710") (pin "1") (pinfunction "1_1") (pintype "passive"))
      (node (ref "L1") (pin "1") (pinfunction "1_1") (pintype "passive"))
      (node (ref "VD710") (pin "1") (pinfunction "C_1") (pintype "passive"))
      (node (ref "VD711") (pin "2") (pinfunction "A_2") (pintype "passive"))
    )
    (net (code "13") (name "GNDA") (class "Default")
      (node (ref "C701") (pin "2") (pinfunction "2_2") (pintype "passive"))
      (node (ref "C702") (pin "1") (pinfunction "1_1") (pintype "passive"))
      (node (ref "C711") (pin "1") (pinfunction "1_1") (pintype "passive"))
      (node (ref "C712") (pin "1") (pinfunction "1_1") (pintype "passive"))
      (node (ref "C713") (pin "1") (pinfunction "1_1") (pintype "passive"))
      (node (ref "C714") (pin "1") (pinfunction "1_1") (pintype "passive"))
      (node (ref "C715") (pin "1") (pinfunction "1_1") (pintype "passive"))
      (node (ref "C716") (pin "2") (pinfunction "2_2") (pintype "passive"))
      (node (ref "C717") (pin "1") (pinfunction "1_1") (pintype "passive"))
      (node (ref "C718") (pin "1") (pinfunction "1_1") (pintype "passive"))
      (node (ref "C719") (pin "1") (pinfunction "1_1") (pintype "passive"))
      (node (ref "C720") (pin "1") (pinfunction "1_1") (pintype "passive"))
      (node (ref "C721") (pin "1") (pinfunction "1_1") (pintype "passive"))
      (node (ref "C722") (pin "1") (pinfunction "1_1") (pintype "passive"))
      (node (ref "C723") (pin "1") (pinfunction "1_1") (pintype "passive"))
      (node (ref "C724") (pin "1") (pinfunction "1_1") (pintype "passive"))
      (node (ref "C725") (pin "1") (pinfunction "1_1") (pintype "passive"))
      (node (ref "C726") (pin "1") (pinfunction "1_1") (pintype "passive"))
      (node (ref "C727") (pin "1") (pinfunction "1_1") (pintype "passive"))
      (node (ref "C728") (pin "1") (pinfunction "1_1") (pintype "passive"))
      (node (ref "C729") (pin "1") (pinfunction "1_1") (pintype "passive"))
      (node (ref "C730") (pin "1") (pinfunction "1_1") (pintype "passive"))
      (node (ref "C731") (pin "1") (pinfunction "1_1") (pintype "passive"))
      (node (ref "C732") (pin "1") (pinfunction "1_1") (pintype "passive"))
      (node (ref "C733") (pin "1") (pinfunction "1_1") (pintype "passive"))
      (node (ref "C734") (pin "1") (pinfunction "1_1") (pintype "passive"))
      (node (ref "C735") (pin "1") (pinfunction "1_1") (pintype "passive"))
      (node (ref "C736") (pin "1") (pinfunction "1_1") (pintype "passive"))
      (node (ref "C737") (pin "2") (pinfunction "2_2") (pintype "passive"))
      (node (ref "C739") (pin "1") (pinfunction "1_1") (pintype "passive"))
      (node (ref "L1") (pin "2") (pinfunction "2_2") (pintype "passive"))
      (node (ref "R703") (pin "1") (pinfunction "1_1") (pintype "passive"))
      (node (ref "R704") (pin "1") (pinfunction "1_1") (pintype "passive"))
      (node (ref "R707") (pin "1") (pinfunction "1_1") (pintype "passive"))
      (node (ref "R709") (pin "2") (pinfunction "2_2") (pintype "passive"))
      (node (ref "R713") (pin "1") (pinfunction "1_1") (pintype "passive"))
      (node (ref "VD701") (pin "2") (pinfunction "2_2") (pintype "passive"))
      (node (ref "VD702") (pin "2") (pinfunction "2_2") (pintype "passive"))
      (node (ref "VD705") (pin "2") (pinfunction "2_2") (pintype "passive"))
      (node (ref "VD706") (pin "2") (pinfunction "2_2") (pintype "passive"))
      (node (ref "VD710") (pin "2") (pinfunction "A_2") (pintype "passive"))
      (node (ref "VD711") (pin "1") (pinfunction "C_1") (pintype "passive"))
      (node (ref "VD712") (pin "1") (pinfunction "C_1") (pintype "passive"))
      (node (ref "VD713") (pin "2") (pinfunction "A_2") (pintype "passive"))
      (node (ref "VD716") (pin "2") (pinfunction "A_2") (pintype "passive"))
      (node (ref "VD717") (pin "1") (pinfunction "C_1") (pintype "passive"))
      (node (ref "XP701") (pin "5") (pinfunction "5_5") (pintype "passive"))
      (node (ref "XP702") (pin "2") (pinfunction "2_2") (pintype "passive"))
    )
    (net (code "14") (name "GNDS") (class "Default")
      (node (ref "R709") (pin "1") (pinfunction "1_1") (pintype "passive"))
      (node (ref "R710") (pin "2") (pinfunction "2_2") (pintype "passive"))
      (node (ref "XP702") (pin "5") (pinfunction "5_5") (pintype "passive"))
    )
    (net (code "15") (name "Net-(DA701-+IN)") (class "Default")
      (node (ref "C737") (pin "1") (pinfunction "1_1") (pintype "passive"))
      (node (ref "DA701") (pin "3") (pinfunction "+IN_3") (pintype "passive"))
      (node (ref "R710") (pin "1") (pinfunction "1_1") (pintype "passive"))
      (node (ref "VD712") (pin "2") (pinfunction "A_2") (pintype "passive"))
      (node (ref "VD713") (pin "1") (pinfunction "C_1") (pintype "passive"))
    )
    (net (code "16") (name "Net-(DA701--IN)") (class "Default")
      (node (ref "C738") (pin "1") (pinfunction "1_1") (pintype "passive"))
      (node (ref "DA701") (pin "2") (pinfunction "-IN_2") (pintype "passive"))
      (node (ref "R711") (pin "2") (pinfunction "2_2") (pintype "passive"))
      (node (ref "VD714") (pin "1") (pinfunction "C_1") (pintype "passive"))
      (node (ref "VD715") (pin "2") (pinfunction "A_2") (pintype "passive"))
    )
    (net (code "17") (name "Net-(DA701-OUT)") (class "Default")
      (node (ref "C738") (pin "2") (pinfunction "2_2") (pintype "passive"))
      (node (ref "DA701") (pin "6") (pinfunction "OUT_6") (pintype "passive"))
      (node (ref "R712") (pin "2") (pinfunction "2_2") (pintype "passive"))
    )
    (net (code "18") (name "Net-(R701-Pad2)") (class "Default")
      (node (ref "R701") (pin "2") (pinfunction "2_2") (pintype "passive"))
      (node (ref "VD701") (pin "1") (pinfunction "1_1") (pintype "passive"))
    )
    (net (code "19") (name "Net-(R702-Pad2)") (class "Default")
      (node (ref "R702") (pin "2") (pinfunction "2_2") (pintype "passive"))
      (node (ref "VD702") (pin "1") (pinfunction "1_1") (pintype "passive"))
    )
    (net (code "20") (name "Net-(R703-Pad2)") (class "Default")
      (node (ref "R703") (pin "2") (pinfunction "2_2") (pintype "passive"))
      (node (ref "VD703") (pin "1") (pinfunction "1_1") (pintype "passive"))
    )
    (net (code "21") (name "Net-(R704-Pad2)") (class "Default")
      (node (ref "R704") (pin "2") (pinfunction "2_2") (pintype "passive"))
      (node (ref "VD704") (pin "1") (pinfunction "1_1") (pintype "passive"))
    )
    (net (code "22") (name "Net-(R705-Pad2)") (class "Default")
      (node (ref "R705") (pin "2") (pinfunction "2_2") (pintype "passive"))
      (node (ref "VD705") (pin "1") (pinfunction "1_1") (pintype "passive"))
    )
    (net (code "23") (name "Net-(R706-Pad2)") (class "Default")
      (node (ref "R706") (pin "2") (pinfunction "2_2") (pintype "passive"))
      (node (ref "VD706") (pin "1") (pinfunction "1_1") (pintype "passive"))
    )
    (net (code "24") (name "Net-(R707-Pad2)") (class "Default")
      (node (ref "R707") (pin "2") (pinfunction "2_2") (pintype "passive"))
      (node (ref "VD707") (pin "1") (pinfunction "1_1") (pintype "passive"))
    )
    (net (code "25") (name "unconnected-(VD704-Pad2)") (class "Default")
      (node (ref "VD704") (pin "2") (pinfunction "2_2") (pintype "passive"))
    )
  )
)
